# Altimeter.net
KiCad netlist of a schematic drawn in Altium Designer
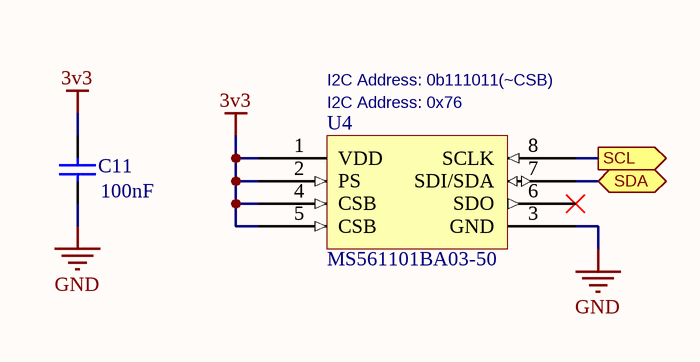
[diagram p0: Altimeter.SchDoc]

(export (version "E")
  (design (tool "Eeschema 10.0.6"))
  (components
    (comp (ref "C11")
      (value "GRM155R71E104KE14D")
      (footprint "Capacitor_0402")
      (description "Chip Capacitor 100nF 0402 25V X7R")
      (fields (field (name "CAPACITANCE") "100nF"))
      (libsource (lib "RIT Launch Initiative") (part "CAPACITOR"))
    )
    (comp (ref "U4")
      (value "MS561101BA03-50")
      (footprint "MS561101BA03-50-Footprint-1")
      (description "Pressure Sensor 1.44V to 3.6V 0.01bar to 1.2bar Absolute 8-Pin QFN T/R")
      (libsource (lib "RIT Launch Initiative") (part "MS561101BA03-50-Symbol-1"))
    )
  )
  (nets
    (net (code "1") (name "/SCL") (class "Default")
      (node (ref "U4") (pin "8") (pinfunction "SCLK_8") (pintype "input"))
    )
    (net (code "2") (name "/SDA") (class "Default")
      (node (ref "U4") (pin "7") (pinfunction "SDI/SDA_7") (pintype "bidirectional"))
    )
    (net (code "3") (name "3v3") (class "Default")
      (node (ref "C11") (pin "2") (pinfunction "2_2") (pintype "passive"))
      (node (ref "U4") (pin "1") (pinfunction "VDD_1") (pintype "power_in"))
      (node (ref "U4") (pin "2") (pinfunction "PS_2") (pintype "input"))
      (node (ref "U4") (pin "4") (pinfunction "CSB_4") (pintype "input"))
      (node (ref "U4") (pin "5") (pinfunction "CSB_5") (pintype "input"))
    )
    (net (code "4") (name "GND") (class "Default")
      (node (ref "C11") (pin "1") (pinfunction "1_1") (pintype "passive"))
      (node (ref "U4") (pin "3") (pinfunction "GND_3") (pintype "power_in"))
    )
    (net (code "5") (name "unconnected-(U4-SDO-Pad6)") (class "Default")
      (node (ref "U4") (pin "6") (pinfunction "SDO_6") (pintype "output+no_connect"))
    )
  )
)
